# MS6205-Arduino.net
KiCad netlist of a schematic drawn in EAGLE
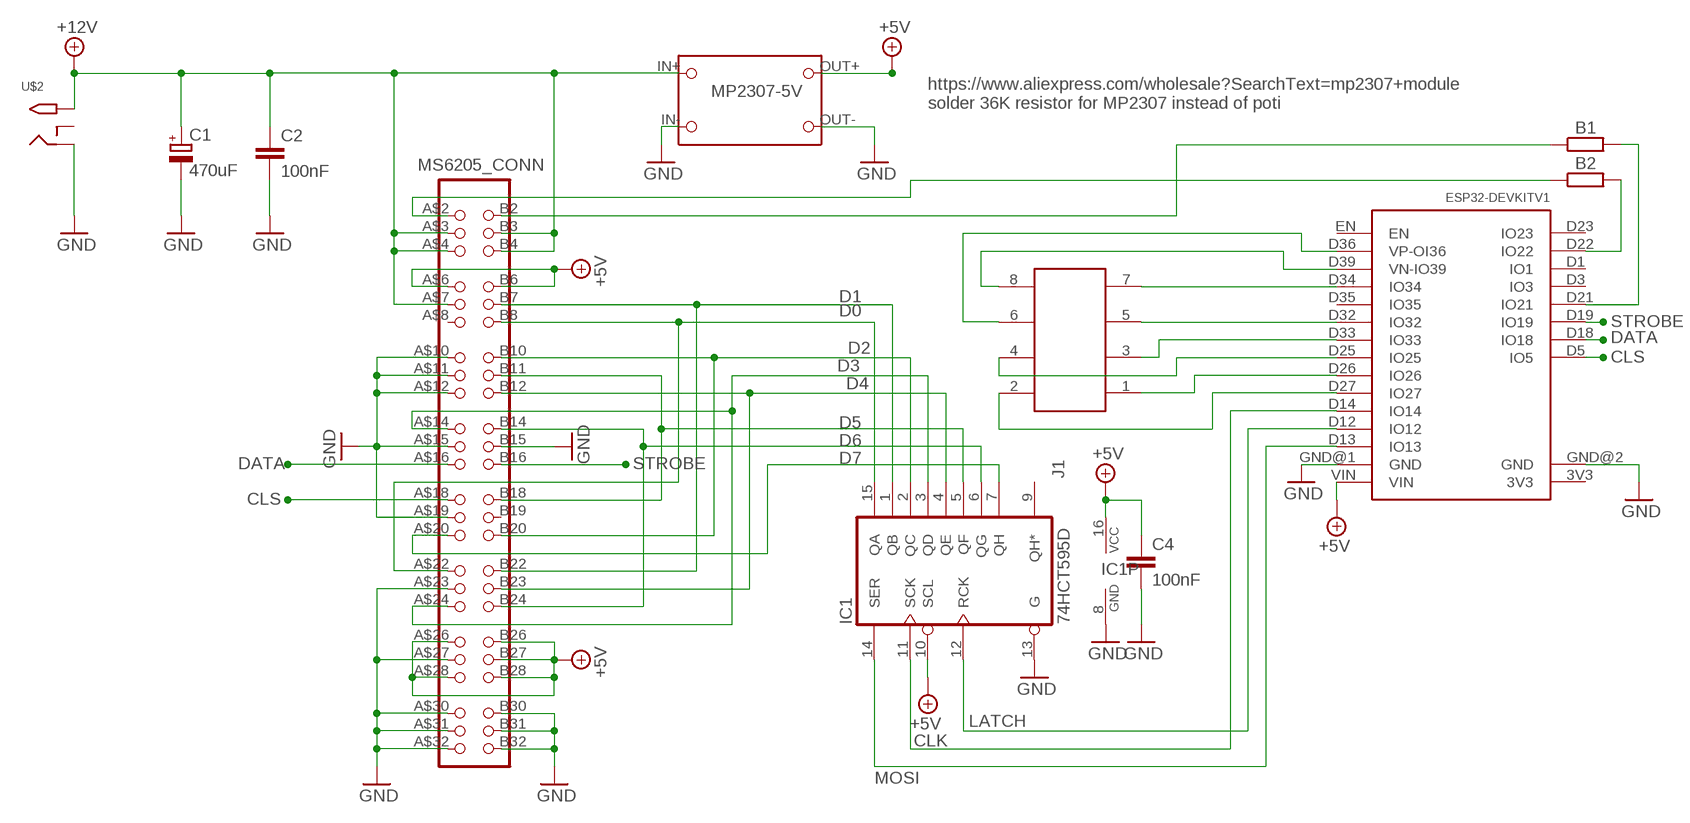
[diagram p0: schematic, sheet 1]

(export (version "E")
  (design (tool "Eeschema 10.0.6"))
  (components
    (comp (ref "B1")
      (value "0")
      (footprint "eagle-import:0204_5")
      (libsource (lib "eagle-import") (part "R-EU_0204/5"))
    )
    (comp (ref "B2")
      (value "0")
      (footprint "eagle-import:0204_5")
      (libsource (lib "eagle-import") (part "R-EU_0204/5"))
    )
    (comp (ref "C1")
      (value "470uF")
      (footprint "eagle-import:150CLZ-1010")
      (libsource (lib "eagle-import") (part "CPOL-EU150CLZ-1010"))
    )
    (comp (ref "C2")
      (value "100nF")
      (footprint "eagle-import:C0805")
      (libsource (lib "eagle-import") (part "C-EUC0805"))
    )
    (comp (ref "C4")
      (value "100nF")
      (footprint "eagle-import:C0805")
      (libsource (lib "eagle-import") (part "C-EUC0805"))
    )
    (comp (ref "IC1")
      (value "74HCT595D")
      (footprint "eagle-import:SO16")
      (libsource (lib "eagle-import") (part "74595DHCT"))
    )
    (comp (ref "J1")
      (value "61200822323")
      (footprint "eagle-import:61200822323")
      (libsource (lib "eagle-import") (part "61200822323"))
    )
    (comp (ref "MP2307-5V")
      (value "PWS-MP2307")
      (footprint "eagle-import:MP2307-PWS")
      (libsource (lib "eagle-import") (part "PWS-MP2307"))
    )
    (comp (ref "U$1")
      (value "ESP32DEVKIT1-REDUCED")
      (footprint "eagle-import:ESP32-DEVKIT1-REDUCED")
      (fields (field (name "SPICEPREFIX") "X"))
      (libsource (lib "eagle-import") (part "ESP32DEVKIT1-REDUCED"))
    )
    (comp (ref "U$2")
      (value "2.1MMJACKTHM")
      (footprint "eagle-import:PJ-102A")
      (libsource (lib "eagle-import") (part "2.1MMJACKTHM"))
    )
    (comp (ref "U$4")
      (value "MS6205_CONN")
      (footprint "eagle-import:MS6205_CONNECTOR_SMD")
      (libsource (lib "eagle-import") (part "MS6205-CONNECTOR"))
    )
  )
  (nets
    (net (code "1") (name "+5V") (class "Default")
      (node (ref "C4") (pin "1") (pinfunction "1_1") (pintype "passive"))
      (node (ref "IC1") (pin "10") (pinfunction "SCL_10") (pintype "input"))
      (node (ref "IC1") (pin "16") (pinfunction "VCC_16") (pintype "power_in"))
      (node (ref "MP2307-5V") (pin "OUT+") (pinfunction "OUT+_OUT+") (pintype "output"))
      (node (ref "U$1") (pin "VIN") (pinfunction "VIN_VIN") (pintype "bidirectional"))
      (node (ref "U$4") (pin "A$26") (pinfunction "A26_A$26") (pintype "passive"))
      (node (ref "U$4") (pin "A$28") (pinfunction "A28_A$28") (pintype "passive"))
      (node (ref "U$4") (pin "A$6") (pinfunction "A6_A$6") (pintype "passive"))
      (node (ref "U$4") (pin "B26") (pinfunction "B26_B26") (pintype "passive"))
      (node (ref "U$4") (pin "B27") (pinfunction "B27_B27") (pintype "passive"))
      (node (ref "U$4") (pin "B28") (pinfunction "B28_B28") (pintype "passive"))
      (node (ref "U$4") (pin "B6") (pinfunction "B6_B6") (pintype "passive"))
    )
    (net (code "2") (name "+12V") (class "Default")
      (node (ref "C1") (pin "+") (pinfunction "+_+") (pintype "passive"))
      (node (ref "C2") (pin "1") (pinfunction "1_1") (pintype "passive"))
      (node (ref "MP2307-5V") (pin "IN+") (pinfunction "IN+_IN+") (pintype "input"))
      (node (ref "U$2") (pin "TIP") (pinfunction "TIP_TIP") (pintype "bidirectional"))
      (node (ref "U$4") (pin "A$3") (pinfunction "A3_A$3") (pintype "passive"))
      (node (ref "U$4") (pin "A$4") (pinfunction "A4_A$4") (pintype "passive"))
      (node (ref "U$4") (pin "A$7") (pinfunction "A7_A$7") (pintype "passive"))
      (node (ref "U$4") (pin "B3") (pinfunction "B3_B3") (pintype "passive"))
      (node (ref "U$4") (pin "B4") (pinfunction "B4_B4") (pintype "passive"))
    )
    (net (code "3") (name "/CLK") (class "Default")
      (node (ref "IC1") (pin "11") (pinfunction "SCK_11") (pintype "input"))
      (node (ref "U$1") (pin "D14") (pinfunction "IO14_D14") (pintype "bidirectional"))
    )
    (net (code "4") (name "/CLS") (class "Default")
      (node (ref "U$1") (pin "D5") (pinfunction "IO5_D5") (pintype "bidirectional"))
      (node (ref "U$4") (pin "A$18") (pinfunction "A18_A$18") (pintype "passive"))
    )
    (net (code "5") (name "/D0") (class "Default")
      (node (ref "IC1") (pin "15") (pinfunction "QA_15") (pintype "tri_state"))
      (node (ref "U$4") (pin "A$22") (pinfunction "A22_A$22") (pintype "passive"))
      (node (ref "U$4") (pin "B8") (pinfunction "B8_B8") (pintype "passive"))
    )
    (net (code "6") (name "/D1") (class "Default")
      (node (ref "IC1") (pin "1") (pinfunction "QB_1") (pintype "tri_state"))
      (node (ref "U$4") (pin "B22") (pinfunction "B22_B22") (pintype "passive"))
      (node (ref "U$4") (pin "B7") (pinfunction "B7_B7") (pintype "passive"))
    )
    (net (code "7") (name "/D2") (class "Default")
      (node (ref "IC1") (pin "2") (pinfunction "QC_2") (pintype "tri_state"))
      (node (ref "U$4") (pin "B10") (pinfunction "B10_B10") (pintype "passive"))
      (node (ref "U$4") (pin "B20") (pinfunction "B20_B20") (pintype "passive"))
    )
    (net (code "8") (name "/D3") (class "Default")
      (node (ref "IC1") (pin "3") (pinfunction "QD_3") (pintype "tri_state"))
      (node (ref "U$4") (pin "A$14") (pinfunction "A14_A$14") (pintype "passive"))
      (node (ref "U$4") (pin "A$24") (pinfunction "A24_A$24") (pintype "passive"))
    )
    (net (code "9") (name "/D4") (class "Default")
      (node (ref "IC1") (pin "4") (pinfunction "QE_4") (pintype "tri_state"))
      (node (ref "U$4") (pin "B12") (pinfunction "B12_B12") (pintype "passive"))
      (node (ref "U$4") (pin "B23") (pinfunction "B23_B23") (pintype "passive"))
    )
    (net (code "10") (name "/D5") (class "Default")
      (node (ref "IC1") (pin "5") (pinfunction "QF_5") (pintype "tri_state"))
      (node (ref "U$4") (pin "B11") (pinfunction "B11_B11") (pintype "passive"))
      (node (ref "U$4") (pin "B18") (pinfunction "B18_B18") (pintype "passive"))
    )
    (net (code "11") (name "/D6") (class "Default")
      (node (ref "IC1") (pin "6") (pinfunction "QG_6") (pintype "tri_state"))
      (node (ref "U$4") (pin "B14") (pinfunction "B14_B14") (pintype "passive"))
      (node (ref "U$4") (pin "B24") (pinfunction "B24_B24") (pintype "passive"))
    )
    (net (code "12") (name "/D7") (class "Default")
      (node (ref "IC1") (pin "7") (pinfunction "QH_7") (pintype "tri_state"))
      (node (ref "U$4") (pin "A$20") (pinfunction "A20_A$20") (pintype "passive"))
    )
    (net (code "13") (name "/DATA") (class "Default")
      (node (ref "U$1") (pin "D18") (pinfunction "IO18_D18") (pintype "bidirectional"))
      (node (ref "U$4") (pin "A$16") (pinfunction "A16_A$16") (pintype "passive"))
    )
    (net (code "14") (name "/LATCH") (class "Default")
      (node (ref "IC1") (pin "12") (pinfunction "RCK_12") (pintype "input"))
      (node (ref "U$1") (pin "D12") (pinfunction "IO12_D12") (pintype "bidirectional"))
    )
    (net (code "15") (name "/MOSI") (class "Default")
      (node (ref "IC1") (pin "14") (pinfunction "SER_14") (pintype "input"))
      (node (ref "U$1") (pin "D13") (pinfunction "IO13_D13") (pintype "bidirectional"))
    )
    (net (code "16") (name "/STROBE") (class "Default")
      (node (ref "U$1") (pin "D19") (pinfunction "IO19_D19") (pintype "bidirectional"))
      (node (ref "U$4") (pin "B16") (pinfunction "B16_B16") (pintype "passive"))
    )
    (net (code "17") (name "GND") (class "Default")
      (node (ref "C1") (pin "-") (pinfunction "-_-") (pintype "passive"))
      (node (ref "C2") (pin "2") (pinfunction "2_2") (pintype "passive"))
      (node (ref "C4") (pin "2") (pinfunction "2_2") (pintype "passive"))
      (node (ref "IC1") (pin "13") (pinfunction "G_13") (pintype "input"))
      (node (ref "IC1") (pin "8") (pinfunction "GND_8") (pintype "power_in"))
      (node (ref "MP2307-5V") (pin "IN-") (pinfunction "IN-_IN-") (pintype "input"))
      (node (ref "MP2307-5V") (pin "OUT-") (pinfunction "OUT-_OUT-") (pintype "output"))
      (node (ref "U$1") (pin "GND@1") (pinfunction "GND_GND@1") (pintype "bidirectional"))
      (node (ref "U$1") (pin "GND@2") (pinfunction "GND_GND@2") (pintype "bidirectional"))
      (node (ref "U$2") (pin "RING") (pinfunction "RING_RING") (pintype "bidirectional"))
      (node (ref "U$4") (pin "A$10") (pinfunction "A10_A$10") (pintype "passive"))
      (node (ref "U$4") (pin "A$11") (pinfunction "A11_A$11") (pintype "passive"))
      (node (ref "U$4") (pin "A$12") (pinfunction "A12_A$12") (pintype "passive"))
      (node (ref "U$4") (pin "A$15") (pinfunction "A15_A$15") (pintype "passive"))
      (node (ref "U$4") (pin "A$19") (pinfunction "A19_A$19") (pintype "passive"))
      (node (ref "U$4") (pin "A$23") (pinfunction "A23_A$23") (pintype "passive"))
      (node (ref "U$4") (pin "A$27") (pinfunction "A27_A$27") (pintype "passive"))
      (node (ref "U$4") (pin "A$30") (pinfunction "A30_A$30") (pintype "passive"))
      (node (ref "U$4") (pin "A$31") (pinfunction "A31_A$31") (pintype "passive"))
      (node (ref "U$4") (pin "A$32") (pinfunction "A32_A$32") (pintype "passive"))
      (node (ref "U$4") (pin "B15") (pinfunction "B15_B15") (pintype "passive"))
      (node (ref "U$4") (pin "B30") (pinfunction "B30_B30") (pintype "passive"))
      (node (ref "U$4") (pin "B31") (pinfunction "B31_B31") (pintype "passive"))
      (node (ref "U$4") (pin "B32") (pinfunction "B32_B32") (pintype "passive"))
    )
    (net (code "18") (name "Net-(B1-Pad1)") (class "Default")
      (node (ref "B1") (pin "1") (pinfunction "1_1") (pintype "passive"))
      (node (ref "U$4") (pin "B2") (pinfunction "B2_B2") (pintype "passive"))
    )
    (net (code "19") (name "Net-(U$1-IO21)") (class "Default")
      (node (ref "B1") (pin "2") (pinfunction "2_2") (pintype "passive"))
      (node (ref "U$1") (pin "D21") (pinfunction "IO21_D21") (pintype "bidirectional"))
    )
    (net (code "20") (name "Net-(U$1-IO22)") (class "Default")
      (node (ref "B2") (pin "2") (pinfunction "2_2") (pintype "passive"))
      (node (ref "U$1") (pin "D22") (pinfunction "IO22_D22") (pintype "bidirectional"))
    )
    (net (code "21") (name "Net-(U$1-IO25)") (class "Default")
      (node (ref "J1") (pin "4") (pinfunction "4_4") (pintype "passive"))
      (node (ref "U$1") (pin "D25") (pinfunction "IO25_D25") (pintype "bidirectional"))
    )
    (net (code "22") (name "Net-(U$1-IO26)") (class "Default")
      (node (ref "J1") (pin "1") (pinfunction "1_1") (pintype "passive"))
      (node (ref "U$1") (pin "D26") (pinfunction "IO26_D26") (pintype "bidirectional"))
    )
    (net (code "23") (name "Net-(U$1-IO27)") (class "Default")
      (node (ref "J1") (pin "2") (pinfunction "2_2") (pintype "passive"))
      (node (ref "U$1") (pin "D27") (pinfunction "IO27_D27") (pintype "bidirectional"))
    )
    (net (code "24") (name "Net-(U$1-IO32)") (class "Default")
      (node (ref "J1") (pin "5") (pinfunction "5_5") (pintype "passive"))
      (node (ref "U$1") (pin "D32") (pinfunction "IO32_D32") (pintype "bidirectional"))
    )
    (net (code "25") (name "Net-(U$1-IO33)") (class "Default")
      (node (ref "J1") (pin "3") (pinfunction "3_3") (pintype "passive"))
      (node (ref "U$1") (pin "D33") (pinfunction "IO33_D33") (pintype "bidirectional"))
    )
    (net (code "26") (name "Net-(U$1-IO34)") (class "Default")
      (node (ref "J1") (pin "7") (pinfunction "7_7") (pintype "passive"))
      (node (ref "U$1") (pin "D34") (pinfunction "IO34_D34") (pintype "bidirectional"))
    )
    (net (code "27") (name "Net-(U$1-VN-IO39)") (class "Default")
      (node (ref "J1") (pin "8") (pinfunction "8_8") (pintype "passive"))
      (node (ref "U$1") (pin "D39") (pinfunction "VN-IO39_D39") (pintype "bidirectional"))
    )
    (net (code "28") (name "Net-(U$1-VP-OI36)") (class "Default")
      (node (ref "J1") (pin "6") (pinfunction "6_6") (pintype "passive"))
      (node (ref "U$1") (pin "D36") (pinfunction "VP-OI36_D36") (pintype "bidirectional"))
    )
    (net (code "29") (name "Net-(U$4-A2)") (class "Default")
      (node (ref "B2") (pin "1") (pinfunction "1_1") (pintype "passive"))
      (node (ref "U$4") (pin "A$2") (pinfunction "A2_A$2") (pintype "passive"))
    )
    (net (code "30") (name "unconnected-(IC1A-QH*-Pad9)") (class "Default")
      (node (ref "IC1") (pin "9") (pinfunction "QH*_9") (pintype "tri_state"))
    )
    (net (code "31") (name "unconnected-(U$1-IO1-PadD1)") (class "Default")
      (node (ref "U$1") (pin "D1") (pinfunction "IO1_D1") (pintype "bidirectional"))
    )
    (net (code "32") (name "unconnected-(U$1-IO3-PadD3)") (class "Default")
      (node (ref "U$1") (pin "D3") (pinfunction "IO3_D3") (pintype "bidirectional"))
    )
    (net (code "33") (name "unconnected-(U$1-IO23-PadD23)") (class "Default")
      (node (ref "U$1") (pin "D23") (pinfunction "IO23_D23") (pintype "bidirectional"))
    )
    (net (code "34") (name "unconnected-(U$1-IO35-PadD35)") (class "Default")
      (node (ref "U$1") (pin "D35") (pinfunction "IO35_D35") (pintype "bidirectional"))
    )
    (net (code "35") (name "unconnected-(U$1-Pad3V3)") (class "Default")
      (node (ref "U$1") (pin "3V3") (pinfunction "3V3_3V3") (pintype "bidirectional"))
    )
    (net (code "36") (name "unconnected-(U$1-PadEN)") (class "Default")
      (node (ref "U$1") (pin "EN") (pinfunction "EN_EN") (pintype "bidirectional"))
    )
    (net (code "37") (name "unconnected-(U$2-PadRING_SW)") (class "Default")
      (node (ref "U$2") (pin "RING_SW") (pinfunction "RING_SW_RING_SW") (pintype "bidirectional"))
    )
    (net (code "38") (name "unconnected-(U$4-A8-PadA$8)") (class "Default")
      (node (ref "U$4") (pin "A$8") (pinfunction "A8_A$8") (pintype "passive"))
    )
    (net (code "39") (name "unconnected-(U$4-PadB19)") (class "Default")
      (node (ref "U$4") (pin "B19") (pinfunction "B19_B19") (pintype "passive"))
    )
  )
)
